# Power.net
KiCad netlist of a schematic drawn in Altium Designer
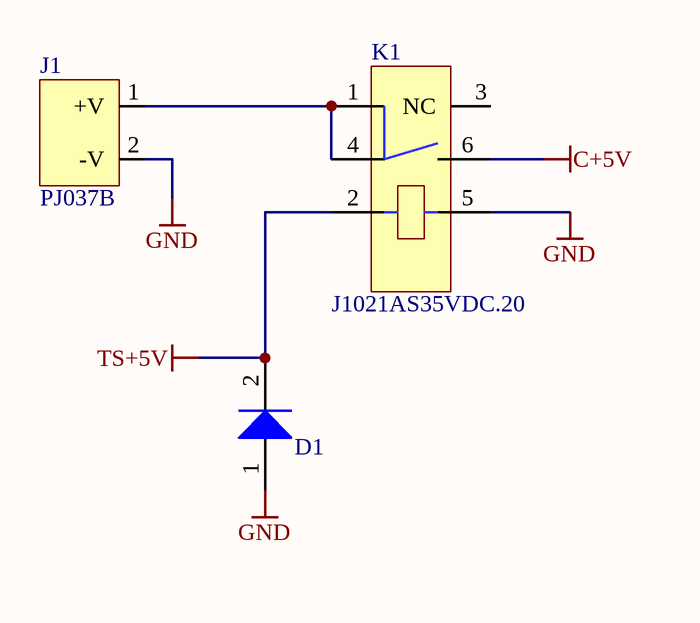
[diagram p0: Power.SchDoc]

(export (version "E")
  (design (tool "Eeschema 10.0.6"))
  (components
    (comp (ref "D1")
      (value "1N4004")
      (footprint "DO41")
      (description "Diode 400 V 1A Through Hole DO-41")
      (fields (field (name "MFG") "Diodes Inc"))
      (libsource (lib "MiscSemi") (part "1N4004"))
    )
    (comp (ref "J1")
      (value "PJ037B")
      (footprint "PJ037B")
      (description "Power Barrel Connector Jack 2.50mm ID (0.098\"), 5.50mm OD (0.217\") Through Hole, Right Angle")
      (fields (field (name "MFG") "CUI"))
      (libsource (lib "APN") (part "PJ037B"))
    )
    (comp (ref "K1")
      (value "J1021AS35VDC.20")
      (footprint "HE7X")
      (description "RELAY GEN PURPOSE SPST 3A 5V")
      (fields (field (name "MFG") "CIT"))
      (libsource (lib "Power") (part "J1021AS35VDC.20"))
    )
  )
  (nets
    (net (code "1") (name "C+5V") (class "Default") (node (ref "K1") (pin "6") (pintype "passive")))
    (net (code "2") (name "GND") (class "Default")
      (node (ref "D1") (pin "1") (pinfunction "A_1") (pintype "passive"))
      (node (ref "J1") (pin "2") (pinfunction "-V_2") (pintype "passive"))
      (node (ref "K1") (pin "5") (pintype "passive"))
    )
    (net (code "3") (name "Net-(J1-+V)") (class "Default")
      (node (ref "J1") (pin "1") (pinfunction "+V_1") (pintype "passive"))
      (node (ref "K1") (pin "1") (pintype "passive"))
      (node (ref "K1") (pin "4") (pintype "passive"))
    )
    (net (code "4") (name "TS+5V") (class "Default")
      (node (ref "D1") (pin "2") (pinfunction "K_2") (pintype "passive"))
      (node (ref "K1") (pin "2") (pintype "passive"))
    )
    (net (code "5") (name "unconnected-(K1-NC-Pad3)") (class "Default")
      (node (ref "K1") (pin "3") (pinfunction "NC_3") (pintype "passive"))
    )
  )
)
